# Inverter_Breakout.net
KiCad netlist of a schematic drawn in Altium Designer
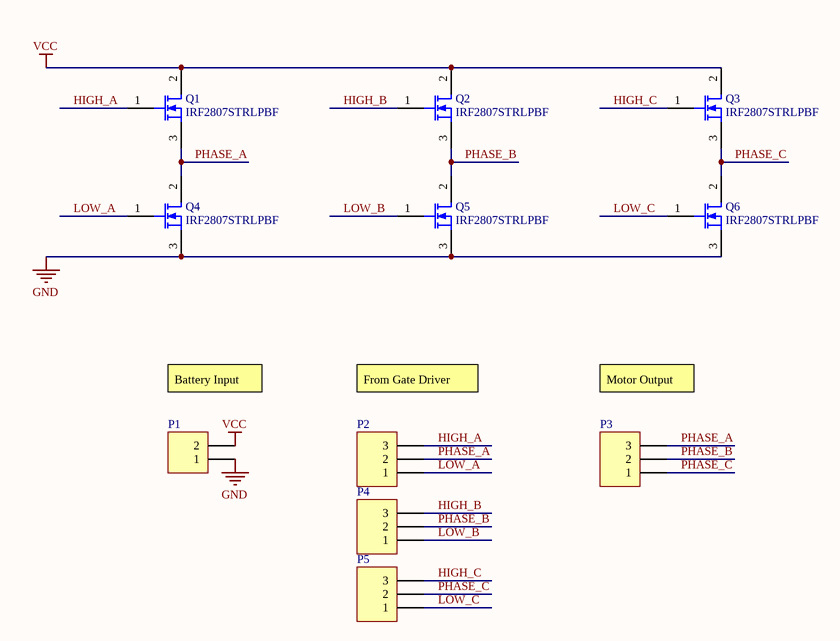
[diagram p0: Inverter_Breakout.SchDoc]

(export (version "E")
  (design (tool "Eeschema 10.0.6"))
  (components
    (comp (ref "P1")
      (value "1x2 Header")
      (footprint "HDR1X2")
      (description "1x2 Pin Header")
      (libsource (lib "GeneralConnectors") (part "1x2 Header"))
    )
    (comp (ref "P2")
      (value "1x3 Header")
      (footprint "HDR1X3")
      (description "1x3 Pin Header")
      (libsource (lib "GeneralConnectors") (part "1x3 Header"))
    )
    (comp (ref "P3")
      (value "1x3 Header")
      (footprint "HDR1X3")
      (description "1x3 Pin Header")
      (libsource (lib "GeneralConnectors") (part "1x3 Header"))
    )
    (comp (ref "P4")
      (value "1x3 Header")
      (footprint "HDR1X3")
      (description "1x3 Pin Header")
      (libsource (lib "GeneralConnectors") (part "1x3 Header"))
    )
    (comp (ref "P5")
      (value "1x3 Header")
      (footprint "HDR1X3")
      (description "1x3 Pin Header")
      (libsource (lib "GeneralConnectors") (part "1x3 Header"))
    )
    (comp (ref "Q1")
      (value "IRF2807STRLPBF")
      (footprint "TO2520AB")
      (fields (field (name "MANUFACTURER") "Infineon"))
      (libsource (lib "General") (part "MOSFET-N"))
    )
    (comp (ref "Q2")
      (value "IRF2807STRLPBF")
      (footprint "TO2520AB")
      (fields (field (name "MANUFACTURER") "Infineon"))
      (libsource (lib "General") (part "MOSFET-N"))
    )
    (comp (ref "Q3")
      (value "IRF2807STRLPBF")
      (footprint "TO2520AB")
      (fields (field (name "MANUFACTURER") "Infineon"))
      (libsource (lib "General") (part "MOSFET-N"))
    )
    (comp (ref "Q4")
      (value "IRF2807STRLPBF")
      (footprint "TO2520AB")
      (fields (field (name "MANUFACTURER") "Infineon"))
      (libsource (lib "General") (part "MOSFET-N"))
    )
    (comp (ref "Q5")
      (value "IRF2807STRLPBF")
      (footprint "TO2520AB")
      (fields (field (name "MANUFACTURER") "Infineon"))
      (libsource (lib "General") (part "MOSFET-N"))
    )
    (comp (ref "Q6")
      (value "IRF2807STRLPBF")
      (footprint "TO2520AB")
      (fields (field (name "MANUFACTURER") "Infineon"))
      (libsource (lib "General") (part "MOSFET-N"))
    )
  )
  (nets
    (net (code "1") (name "/HIGH_A") (class "Default")
      (node (ref "P2") (pin "3") (pinfunction "3_3") (pintype "passive"))
      (node (ref "Q1") (pin "1") (pinfunction "G_1") (pintype "passive"))
    )
    (net (code "2") (name "/HIGH_B") (class "Default")
      (node (ref "P4") (pin "3") (pinfunction "3_3") (pintype "passive"))
      (node (ref "Q2") (pin "1") (pinfunction "G_1") (pintype "passive"))
    )
    (net (code "3") (name "/HIGH_C") (class "Default")
      (node (ref "P5") (pin "3") (pinfunction "3_3") (pintype "passive"))
      (node (ref "Q3") (pin "1") (pinfunction "G_1") (pintype "passive"))
    )
    (net (code "4") (name "/LOW_A") (class "Default")
      (node (ref "P2") (pin "1") (pinfunction "1_1") (pintype "passive"))
      (node (ref "Q4") (pin "1") (pinfunction "G_1") (pintype "passive"))
    )
    (net (code "5") (name "/LOW_B") (class "Default")
      (node (ref "P4") (pin "1") (pinfunction "1_1") (pintype "passive"))
      (node (ref "Q5") (pin "1") (pinfunction "G_1") (pintype "passive"))
    )
    (net (code "6") (name "/LOW_C") (class "Default")
      (node (ref "P5") (pin "1") (pinfunction "1_1") (pintype "passive"))
      (node (ref "Q6") (pin "1") (pinfunction "G_1") (pintype "passive"))
    )
    (net (code "7") (name "/PHASE_A") (class "Default")
      (node (ref "P2") (pin "2") (pinfunction "2_2") (pintype "passive"))
      (node (ref "P3") (pin "3") (pinfunction "3_3") (pintype "passive"))
      (node (ref "Q1") (pin "3") (pinfunction "S_3") (pintype "passive"))
      (node (ref "Q4") (pin "2") (pinfunction "D_2") (pintype "passive"))
    )
    (net (code "8") (name "/PHASE_B") (class "Default")
      (node (ref "P3") (pin "2") (pinfunction "2_2") (pintype "passive"))
      (node (ref "P4") (pin "2") (pinfunction "2_2") (pintype "passive"))
      (node (ref "Q2") (pin "3") (pinfunction "S_3") (pintype "passive"))
      (node (ref "Q5") (pin "2") (pinfunction "D_2") (pintype "passive"))
    )
    (net (code "9") (name "/PHASE_C") (class "Default")
      (node (ref "P3") (pin "1") (pinfunction "1_1") (pintype "passive"))
      (node (ref "P5") (pin "2") (pinfunction "2_2") (pintype "passive"))
      (node (ref "Q3") (pin "3") (pinfunction "S_3") (pintype "passive"))
      (node (ref "Q6") (pin "2") (pinfunction "D_2") (pintype "passive"))
    )
    (net (code "10") (name "GND") (class "Default")
      (node (ref "P1") (pin "1") (pinfunction "1_1") (pintype "passive"))
      (node (ref "Q4") (pin "3") (pinfunction "S_3") (pintype "passive"))
      (node (ref "Q5") (pin "3") (pinfunction "S_3") (pintype "passive"))
      (node (ref "Q6") (pin "3") (pinfunction "S_3") (pintype "passive"))
    )
    (net (code "11") (name "VCC") (class "Default")
      (node (ref "P1") (pin "2") (pinfunction "2_2") (pintype "passive"))
      (node (ref "Q1") (pin "2") (pinfunction "D_2") (pintype "passive"))
      (node (ref "Q2") (pin "2") (pinfunction "D_2") (pintype "passive"))
      (node (ref "Q3") (pin "2") (pinfunction "D_2") (pintype "passive"))
    )
  )
)
